# MegaFDC.net
KiCad netlist of a schematic drawn in EAGLE
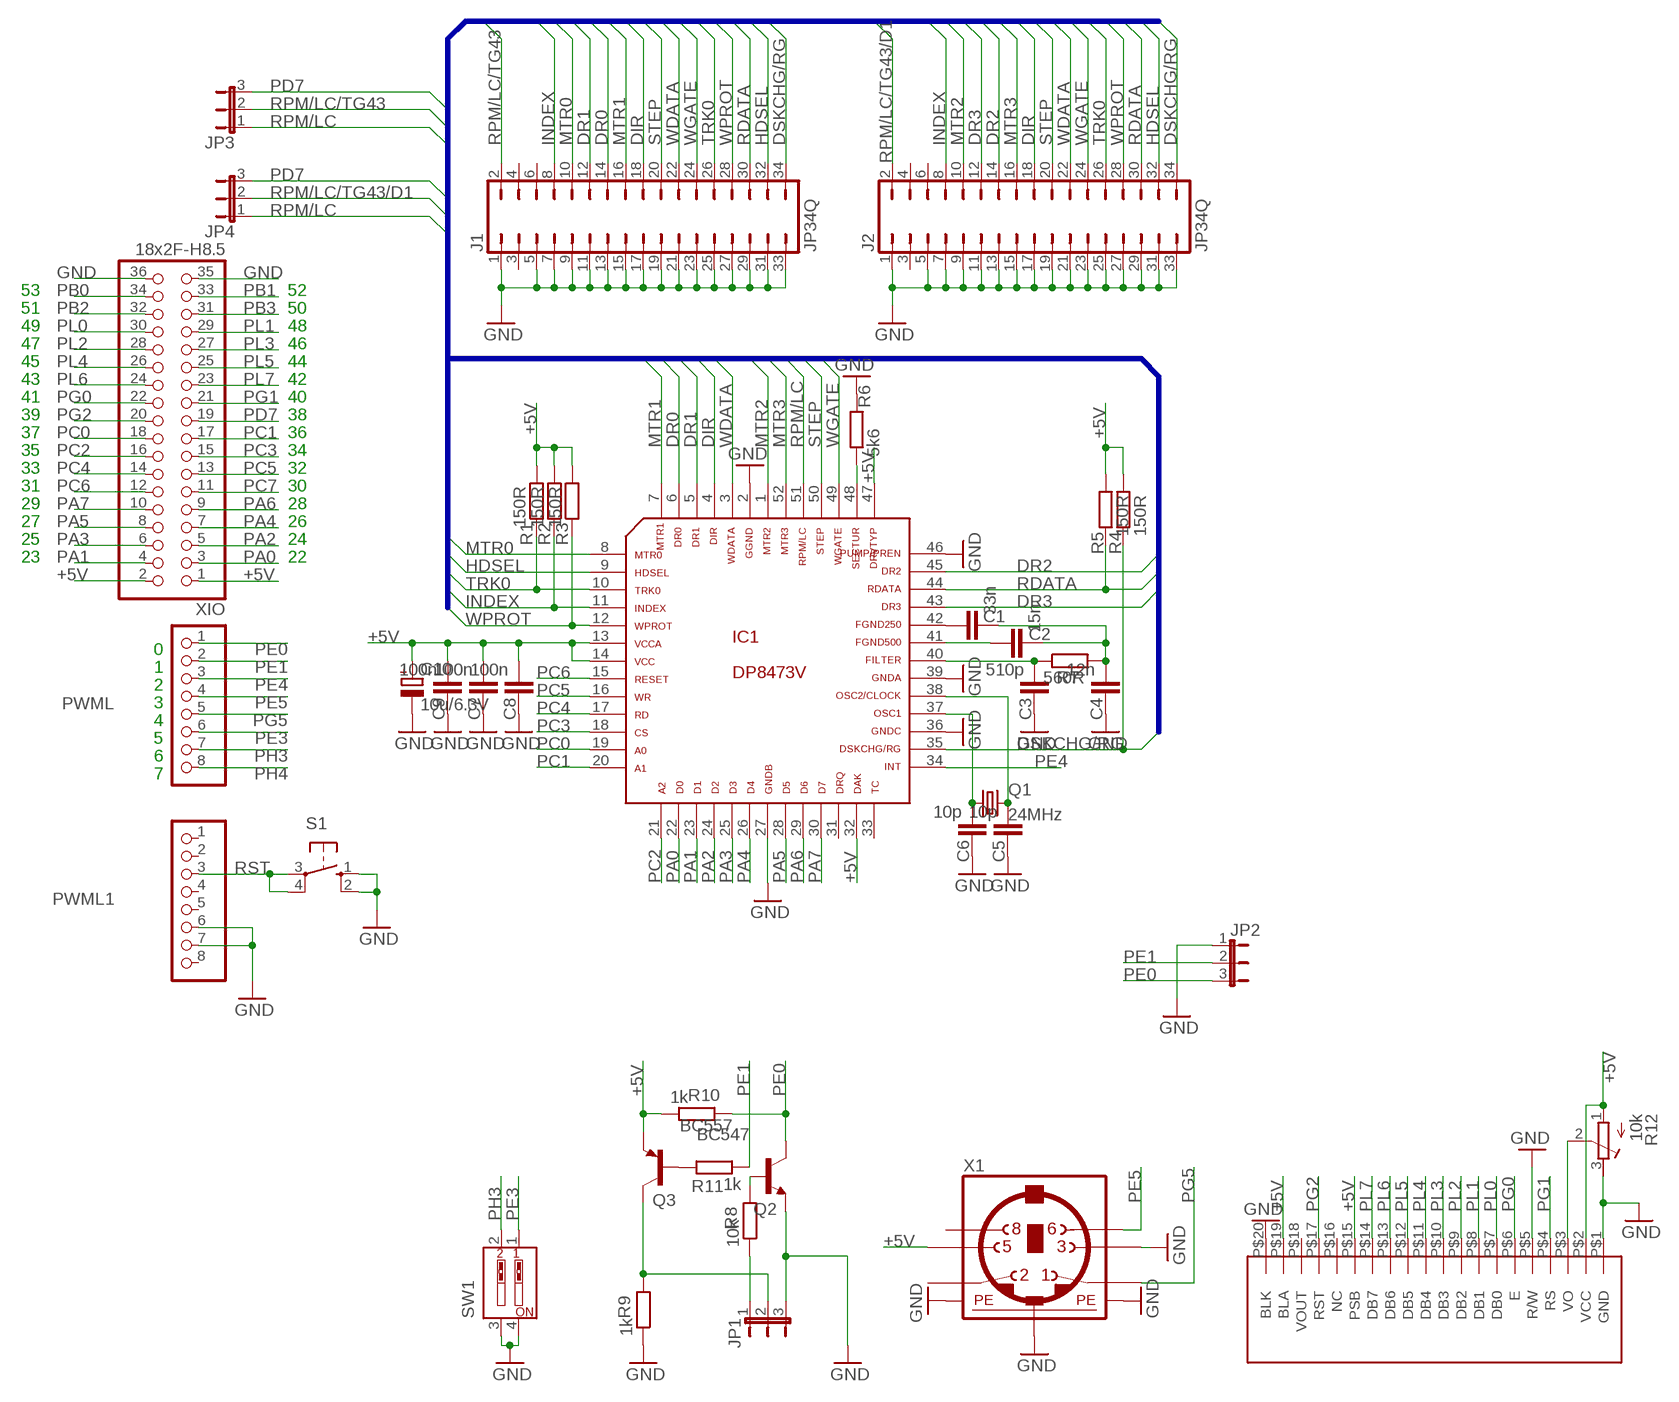
[diagram p0: schematic, sheet 1]

(export (version "E")
  (design (tool "Eeschema 10.0.6"))
  (components
    (comp (ref "C1")
      (value "33n")
      (footprint "eagle-import:C025-025X050")
      (libsource (lib "eagle-import") (part "C-EU025-025X050"))
    )
    (comp (ref "C2")
      (value "15n")
      (footprint "eagle-import:C025-025X050")
      (libsource (lib "eagle-import") (part "C-EU025-025X050"))
    )
    (comp (ref "C3")
      (value "510p")
      (footprint "eagle-import:C025-025X050")
      (libsource (lib "eagle-import") (part "C-EU025-025X050"))
    )
    (comp (ref "C4")
      (value "12n")
      (footprint "eagle-import:C025-025X050")
      (libsource (lib "eagle-import") (part "C-EU025-025X050"))
    )
    (comp (ref "C5")
      (value "10p")
      (footprint "eagle-import:C025-025X050")
      (libsource (lib "eagle-import") (part "C-EU025-025X050"))
    )
    (comp (ref "C6")
      (value "10p")
      (footprint "eagle-import:C025-025X050")
      (libsource (lib "eagle-import") (part "C-EU025-025X050"))
    )
    (comp (ref "C7")
      (value "100n")
      (footprint "eagle-import:C050-025X075")
      (libsource (lib "eagle-import") (part "C-EU050-025X075"))
    )
    (comp (ref "C8")
      (value "100n")
      (footprint "eagle-import:C050-025X075")
      (libsource (lib "eagle-import") (part "C-EU050-025X075"))
    )
    (comp (ref "C9")
      (value "100n")
      (footprint "eagle-import:C050-025X075")
      (libsource (lib "eagle-import") (part "C-EU050-025X075"))
    )
    (comp (ref "C10")
      (value "10u/6.3V")
      (footprint "eagle-import:B45181A")
      (libsource (lib "eagle-import") (part "CPOL-EUB45181A"))
    )
    (comp (ref "IC1")
      (value "DP8473V")
      (footprint "eagle-import:S52")
      (libsource (lib "eagle-import") (part "DP8473V{dblquote}"))
    )
    (comp (ref "J1")
      (value "JP34Q")
      (footprint "eagle-import:JP34Q")
      (libsource (lib "eagle-import") (part "JP34Q"))
    )
    (comp (ref "J2")
      (value "JP34Q")
      (footprint "eagle-import:JP34Q")
      (libsource (lib "eagle-import") (part "JP34Q"))
    )
    (comp (ref "JP1")
      (value "JP2E")
      (footprint "eagle-import:JP2")
      (libsource (lib "eagle-import") (part "JP2E"))
    )
    (comp (ref "JP2")
      (value "JP2E")
      (footprint "eagle-import:JP2")
      (libsource (lib "eagle-import") (part "JP2E"))
    )
    (comp (ref "JP3")
      (value "JP2E")
      (footprint "eagle-import:JP2")
      (libsource (lib "eagle-import") (part "JP2E"))
    )
    (comp (ref "JP4")
      (value "JP2E")
      (footprint "eagle-import:JP2")
      (libsource (lib "eagle-import") (part "JP2E"))
    )
    (comp (ref "PWML")
      (value "8x1F-H8.5")
      (footprint "eagle-import:1X08")
      (libsource (lib "eagle-import") (part "PINHD-1X8"))
    )
    (comp (ref "PWML1")
      (value "8x1F-H8.5")
      (footprint "eagle-import:1X08")
      (libsource (lib "eagle-import") (part "PINHD-1X8"))
    )
    (comp (ref "Q1")
      (value "24MHz")
      (footprint "eagle-import:HC49_S")
      (libsource (lib "eagle-import") (part "CRYSTALHC49S"))
    )
    (comp (ref "Q2")
      (value "BC547")
      (footprint "eagle-import:TO92S")
      (libsource (lib "eagle-import") (part "BC547S"))
    )
    (comp (ref "Q3")
      (value "BC557")
      (footprint "eagle-import:TO92-EBC")
      (libsource (lib "eagle-import") (part "BC557"))
    )
    (comp (ref "R1")
      (value "150R")
      (footprint "eagle-import:0207_7")
      (libsource (lib "eagle-import") (part "R-EU_0207/7"))
    )
    (comp (ref "R2")
      (value "150R")
      (footprint "eagle-import:0207_7")
      (libsource (lib "eagle-import") (part "R-EU_0207/7"))
    )
    (comp (ref "R3")
      (value "150R")
      (footprint "eagle-import:0207_7")
      (libsource (lib "eagle-import") (part "R-EU_0207/7"))
    )
    (comp (ref "R4")
      (value "150R")
      (footprint "eagle-import:0207_7")
      (libsource (lib "eagle-import") (part "R-EU_0207/7"))
    )
    (comp (ref "R5")
      (value "150R")
      (footprint "eagle-import:0207_7")
      (libsource (lib "eagle-import") (part "R-EU_0207/7"))
    )
    (comp (ref "R6")
      (value "5k6")
      (footprint "eagle-import:0207_7")
      (libsource (lib "eagle-import") (part "R-EU_0207/7"))
    )
    (comp (ref "R7")
      (value "560R")
      (footprint "eagle-import:0207_7")
      (libsource (lib "eagle-import") (part "R-EU_0207/7"))
    )
    (comp (ref "R8")
      (value "10k")
      (footprint "eagle-import:0207_7")
      (libsource (lib "eagle-import") (part "R-EU_0207/7"))
    )
    (comp (ref "R9")
      (value "1k")
      (footprint "eagle-import:0207_7")
      (libsource (lib "eagle-import") (part "R-EU_0207/7"))
    )
    (comp (ref "R10")
      (value "1k")
      (footprint "eagle-import:0207_7")
      (libsource (lib "eagle-import") (part "R-EU_0207/7"))
    )
    (comp (ref "R11")
      (value "1k")
      (footprint "eagle-import:0207_7")
      (libsource (lib "eagle-import") (part "R-EU_0207/7"))
    )
    (comp (ref "R12")
      (value "10k")
      (footprint "eagle-import:RTRIM3296Y")
      (libsource (lib "eagle-import") (part "R-TRIMM3296Y"))
    )
    (comp (ref "S1")
      (value "10-XX")
      (footprint "eagle-import:B3F-10XX")
      (fields (field (name "MPN") "B3F-1000"))
      (libsource (lib "eagle-import") (part "10-XX"))
    )
    (comp (ref "SW1")
      (value "DIP2X")
      (footprint "eagle-import:EDG-02")
      (libsource (lib "eagle-import") (part "DIP2X"))
    )
    (comp (ref "U$1")
      (value "W12864")
      (footprint "eagle-import:W12864")
      (libsource (lib "eagle-import") (part "W12864"))
    )
    (comp (ref "X1")
      (value "MINI_DIN_6")
      (footprint "eagle-import:M_DIN6")
      (libsource (lib "eagle-import") (part "MINI_DIN_6"))
    )
    (comp (ref "XIO")
      (value "18x2F-H8.5")
      (footprint "eagle-import:2X18")
      (libsource (lib "eagle-import") (part "PINHD-2X18"))
    )
  )
  (nets
    (net (code "1") (name "/+5V") (class "Default")
      (node (ref "C10") (pin "+") (pinfunction "+_+") (pintype "passive"))
      (node (ref "C7") (pin "2") (pinfunction "2_2") (pintype "passive"))
      (node (ref "C8") (pin "2") (pinfunction "2_2") (pintype "passive"))
      (node (ref "C9") (pin "2") (pinfunction "2_2") (pintype "passive"))
      (node (ref "IC1") (pin "13") (pinfunction "P$13_13") (pintype "bidirectional"))
      (node (ref "IC1") (pin "14") (pinfunction "P$14_14") (pintype "power_in"))
      (node (ref "IC1") (pin "32") (pinfunction "P$32_32") (pintype "bidirectional"))
      (node (ref "IC1") (pin "47") (pinfunction "P$47_47") (pintype "power_in"))
      (node (ref "Q3") (pin "E") (pinfunction "E_E") (pintype "passive"))
      (node (ref "R1") (pin "2") (pinfunction "2_2") (pintype "passive"))
      (node (ref "R10") (pin "1") (pinfunction "1_1") (pintype "passive"))
      (node (ref "R12") (pin "1") (pinfunction "A_1") (pintype "passive"))
      (node (ref "R2") (pin "2") (pinfunction "2_2") (pintype "passive"))
      (node (ref "R3") (pin "2") (pinfunction "2_2") (pintype "passive"))
      (node (ref "R4") (pin "2") (pinfunction "2_2") (pintype "passive"))
      (node (ref "R5") (pin "2") (pinfunction "2_2") (pintype "passive"))
      (node (ref "U$1") (pin "P$15") (pinfunction "PSB_P$15") (pintype "bidirectional"))
      (node (ref "U$1") (pin "P$19") (pinfunction "BLA_P$19") (pintype "bidirectional"))
      (node (ref "U$1") (pin "P$2") (pinfunction "VCC_P$2") (pintype "bidirectional"))
      (node (ref "X1") (pin "5") (pinfunction "5_5") (pintype "passive"))
      (node (ref "XIO") (pin "1") (pinfunction "1_1") (pintype "passive"))
      (node (ref "XIO") (pin "2") (pinfunction "2_2") (pintype "passive"))
    )
    (net (code "2") (name "/DIR") (class "Default")
      (node (ref "IC1") (pin "4") (pinfunction "P$4_4") (pintype "bidirectional"))
      (node (ref "J1") (pin "18") (pinfunction "18_18") (pintype "passive"))
      (node (ref "J2") (pin "18") (pinfunction "18_18") (pintype "passive"))
    )
    (net (code "3") (name "/DR0") (class "Default")
      (node (ref "IC1") (pin "6") (pinfunction "P$6_6") (pintype "bidirectional"))
      (node (ref "J1") (pin "14") (pinfunction "14_14") (pintype "passive"))
    )
    (net (code "4") (name "/DR1") (class "Default")
      (node (ref "IC1") (pin "5") (pinfunction "P$5_5") (pintype "bidirectional"))
      (node (ref "J1") (pin "12") (pinfunction "12_12") (pintype "passive"))
    )
    (net (code "5") (name "/DR2") (class "Default")
      (node (ref "IC1") (pin "45") (pinfunction "P$45_45") (pintype "bidirectional"))
      (node (ref "J2") (pin "14") (pinfunction "14_14") (pintype "passive"))
    )
    (net (code "6") (name "/DR3") (class "Default")
      (node (ref "IC1") (pin "43") (pinfunction "P$43_43") (pintype "bidirectional"))
      (node (ref "J2") (pin "12") (pinfunction "12_12") (pintype "passive"))
    )
    (net (code "7") (name "/DSKCHG{slash}RG") (class "Default")
      (node (ref "IC1") (pin "35") (pinfunction "P$35_35") (pintype "bidirectional"))
      (node (ref "J1") (pin "34") (pinfunction "34_34") (pintype "passive"))
      (node (ref "J2") (pin "34") (pinfunction "34_34") (pintype "passive"))
      (node (ref "R4") (pin "1") (pinfunction "1_1") (pintype "passive"))
    )
    (net (code "8") (name "/HDSEL") (class "Default")
      (node (ref "IC1") (pin "9") (pinfunction "P$9_9") (pintype "bidirectional"))
      (node (ref "J1") (pin "32") (pinfunction "32_32") (pintype "passive"))
      (node (ref "J2") (pin "32") (pinfunction "32_32") (pintype "passive"))
    )
    (net (code "9") (name "/INDEX") (class "Default")
      (node (ref "IC1") (pin "11") (pinfunction "P$11_11") (pintype "bidirectional"))
      (node (ref "J1") (pin "8") (pinfunction "8_8") (pintype "passive"))
      (node (ref "J2") (pin "8") (pinfunction "8_8") (pintype "passive"))
      (node (ref "R2") (pin "1") (pinfunction "1_1") (pintype "passive"))
    )
    (net (code "10") (name "/MTR0") (class "Default")
      (node (ref "IC1") (pin "8") (pinfunction "P$8_8") (pintype "bidirectional"))
      (node (ref "J1") (pin "10") (pinfunction "10_10") (pintype "passive"))
    )
    (net (code "11") (name "/MTR1") (class "Default")
      (node (ref "IC1") (pin "7") (pinfunction "P$7_7") (pintype "bidirectional"))
      (node (ref "J1") (pin "16") (pinfunction "16_16") (pintype "passive"))
    )
    (net (code "12") (name "/MTR2") (class "Default")
      (node (ref "IC1") (pin "1") (pinfunction "P$1_1") (pintype "bidirectional"))
      (node (ref "J2") (pin "10") (pinfunction "10_10") (pintype "passive"))
    )
    (net (code "13") (name "/MTR3") (class "Default")
      (node (ref "IC1") (pin "52") (pinfunction "P$52_52") (pintype "bidirectional"))
      (node (ref "J2") (pin "16") (pinfunction "16_16") (pintype "passive"))
    )
    (net (code "14") (name "/PA0") (class "Default")
      (node (ref "IC1") (pin "22") (pinfunction "P$22_22") (pintype "bidirectional"))
      (node (ref "XIO") (pin "3") (pinfunction "3_3") (pintype "passive"))
    )
    (net (code "15") (name "/PA1") (class "Default")
      (node (ref "IC1") (pin "23") (pinfunction "P$23_23") (pintype "bidirectional"))
      (node (ref "XIO") (pin "4") (pinfunction "4_4") (pintype "passive"))
    )
    (net (code "16") (name "/PA2") (class "Default")
      (node (ref "IC1") (pin "24") (pinfunction "P$24_24") (pintype "bidirectional"))
      (node (ref "XIO") (pin "5") (pinfunction "5_5") (pintype "passive"))
    )
    (net (code "17") (name "/PA3") (class "Default")
      (node (ref "IC1") (pin "25") (pinfunction "P$25_25") (pintype "bidirectional"))
      (node (ref "XIO") (pin "6") (pinfunction "6_6") (pintype "passive"))
    )
    (net (code "18") (name "/PA4") (class "Default")
      (node (ref "IC1") (pin "26") (pinfunction "P$26_26") (pintype "bidirectional"))
      (node (ref "XIO") (pin "7") (pinfunction "7_7") (pintype "passive"))
    )
    (net (code "19") (name "/PA5") (class "Default")
      (node (ref "IC1") (pin "28") (pinfunction "P$28_28") (pintype "bidirectional"))
      (node (ref "XIO") (pin "8") (pinfunction "8_8") (pintype "passive"))
    )
    (net (code "20") (name "/PA6") (class "Default")
      (node (ref "IC1") (pin "29") (pinfunction "P$29_29") (pintype "bidirectional"))
      (node (ref "XIO") (pin "9") (pinfunction "9_9") (pintype "passive"))
    )
    (net (code "21") (name "/PA7") (class "Default")
      (node (ref "IC1") (pin "30") (pinfunction "P$30_30") (pintype "bidirectional"))
      (node (ref "XIO") (pin "10") (pinfunction "10_10") (pintype "passive"))
    )
    (net (code "22") (name "/PB0") (class "Default")
      (node (ref "XIO") (pin "34") (pinfunction "34_34") (pintype "passive"))
    )
    (net (code "23") (name "/PB1") (class "Default")
      (node (ref "XIO") (pin "33") (pinfunction "33_33") (pintype "passive"))
    )
    (net (code "24") (name "/PB2") (class "Default")
      (node (ref "XIO") (pin "32") (pinfunction "32_32") (pintype "passive"))
    )
    (net (code "25") (name "/PB3") (class "Default")
      (node (ref "XIO") (pin "31") (pinfunction "31_31") (pintype "passive"))
    )
    (net (code "26") (name "/PC0") (class "Default")
      (node (ref "IC1") (pin "19") (pinfunction "P$19_19") (pintype "bidirectional"))
      (node (ref "XIO") (pin "18") (pinfunction "18_18") (pintype "passive"))
    )
    (net (code "27") (name "/PC1") (class "Default")
      (node (ref "IC1") (pin "20") (pinfunction "P$20_20") (pintype "bidirectional"))
      (node (ref "XIO") (pin "17") (pinfunction "17_17") (pintype "passive"))
    )
    (net (code "28") (name "/PC2") (class "Default")
      (node (ref "IC1") (pin "21") (pinfunction "P$21_21") (pintype "bidirectional"))
      (node (ref "XIO") (pin "16") (pinfunction "16_16") (pintype "passive"))
    )
    (net (code "29") (name "/PC3") (class "Default")
      (node (ref "IC1") (pin "18") (pinfunction "P$18_18") (pintype "bidirectional"))
      (node (ref "XIO") (pin "15") (pinfunction "15_15") (pintype "passive"))
    )
    (net (code "30") (name "/PC4") (class "Default")
      (node (ref "IC1") (pin "17") (pinfunction "P$17_17") (pintype "bidirectional"))
      (node (ref "XIO") (pin "14") (pinfunction "14_14") (pintype "passive"))
    )
    (net (code "31") (name "/PC5") (class "Default")
      (node (ref "IC1") (pin "16") (pinfunction "P$16_16") (pintype "bidirectional"))
      (node (ref "XIO") (pin "13") (pinfunction "13_13") (pintype "passive"))
    )
    (net (code "32") (name "/PC6") (class "Default")
      (node (ref "IC1") (pin "15") (pinfunction "P$15_15") (pintype "power_in"))
      (node (ref "XIO") (pin "12") (pinfunction "12_12") (pintype "passive"))
    )
    (net (code "33") (name "/PC7") (class "Default")
      (node (ref "XIO") (pin "11") (pinfunction "11_11") (pintype "passive"))
    )
    (net (code "34") (name "/PD7") (class "Default")
      (node (ref "JP3") (pin "3") (pinfunction "3_3") (pintype "passive"))
      (node (ref "JP4") (pin "3") (pinfunction "3_3") (pintype "passive"))
      (node (ref "XIO") (pin "19") (pinfunction "19_19") (pintype "passive"))
    )
    (net (code "35") (name "/PE0") (class "Default")
      (node (ref "JP2") (pin "3") (pinfunction "3_3") (pintype "passive"))
      (node (ref "PWML") (pin "1") (pinfunction "1_1") (pintype "passive"))
      (node (ref "Q2") (pin "3") (pinfunction "C_3") (pintype "passive"))
      (node (ref "R10") (pin "2") (pinfunction "2_2") (pintype "passive"))
    )
    (net (code "36") (name "/PE1") (class "Default")
      (node (ref "JP2") (pin "2") (pinfunction "2_2") (pintype "passive"))
      (node (ref "PWML") (pin "2") (pinfunction "2_2") (pintype "passive"))
      (node (ref "R11") (pin "1") (pinfunction "1_1") (pintype "passive"))
    )
    (net (code "37") (name "/PE3") (class "Default")
      (node (ref "PWML") (pin "6") (pinfunction "6_6") (pintype "passive"))
      (node (ref "SW1") (pin "1") (pinfunction "1_1") (pintype "passive"))
    )
    (net (code "38") (name "/PE4") (class "Default")
      (node (ref "IC1") (pin "34") (pinfunction "P$34_34") (pintype "bidirectional"))
      (node (ref "PWML") (pin "3") (pinfunction "3_3") (pintype "passive"))
    )
    (net (code "39") (name "/PE5") (class "Default")
      (node (ref "PWML") (pin "4") (pinfunction "4_4") (pintype "passive"))
      (node (ref "X1") (pin "6") (pinfunction "6_6") (pintype "passive"))
    )
    (net (code "40") (name "/PG0") (class "Default")
      (node (ref "U$1") (pin "P$6") (pinfunction "E_P$6") (pintype "bidirectional"))
      (node (ref "XIO") (pin "22") (pinfunction "22_22") (pintype "passive"))
    )
    (net (code "41") (name "/PG1") (class "Default")
      (node (ref "U$1") (pin "P$4") (pinfunction "RS_P$4") (pintype "bidirectional"))
      (node (ref "XIO") (pin "21") (pinfunction "21_21") (pintype "passive"))
    )
    (net (code "42") (name "/PG2") (class "Default")
      (node (ref "U$1") (pin "P$17") (pinfunction "RST_P$17") (pintype "bidirectional"))
      (node (ref "XIO") (pin "20") (pinfunction "20_20") (pintype "passive"))
    )
    (net (code "43") (name "/PG5") (class "Default")
      (node (ref "PWML") (pin "5") (pinfunction "5_5") (pintype "passive"))
      (node (ref "X1") (pin "1") (pinfunction "1_1") (pintype "passive"))
    )
    (net (code "44") (name "/PH3") (class "Default")
      (node (ref "PWML") (pin "7") (pinfunction "7_7") (pintype "passive"))
      (node (ref "SW1") (pin "2") (pinfunction "2_2") (pintype "passive"))
    )
    (net (code "45") (name "/PH4") (class "Default")
      (node (ref "PWML") (pin "8") (pinfunction "8_8") (pintype "passive"))
    )
    (net (code "46") (name "/PL0") (class "Default")
      (node (ref "U$1") (pin "P$7") (pinfunction "DB0_P$7") (pintype "bidirectional"))
      (node (ref "XIO") (pin "30") (pinfunction "30_30") (pintype "passive"))
    )
    (net (code "47") (name "/PL1") (class "Default")
      (node (ref "U$1") (pin "P$8") (pinfunction "DB1_P$8") (pintype "bidirectional"))
      (node (ref "XIO") (pin "29") (pinfunction "29_29") (pintype "passive"))
    )
    (net (code "48") (name "/PL2") (class "Default")
      (node (ref "U$1") (pin "P$9") (pinfunction "DB2_P$9") (pintype "bidirectional"))
      (node (ref "XIO") (pin "28") (pinfunction "28_28") (pintype "passive"))
    )
    (net (code "49") (name "/PL3") (class "Default")
      (node (ref "U$1") (pin "P$10") (pinfunction "DB3_P$10") (pintype "bidirectional"))
      (node (ref "XIO") (pin "27") (pinfunction "27_27") (pintype "passive"))
    )
    (net (code "50") (name "/PL4") (class "Default")
      (node (ref "U$1") (pin "P$11") (pinfunction "DB4_P$11") (pintype "bidirectional"))
      (node (ref "XIO") (pin "26") (pinfunction "26_26") (pintype "passive"))
    )
    (net (code "51") (name "/PL5") (class "Default")
      (node (ref "U$1") (pin "P$12") (pinfunction "DB5_P$12") (pintype "bidirectional"))
      (node (ref "XIO") (pin "25") (pinfunction "25_25") (pintype "passive"))
    )
    (net (code "52") (name "/PL6") (class "Default")
      (node (ref "U$1") (pin "P$13") (pinfunction "DB6_P$13") (pintype "bidirectional"))
      (node (ref "XIO") (pin "24") (pinfunction "24_24") (pintype "passive"))
    )
    (net (code "53") (name "/PL7") (class "Default")
      (node (ref "U$1") (pin "P$14") (pinfunction "DB7_P$14") (pintype "bidirectional"))
      (node (ref "XIO") (pin "23") (pinfunction "23_23") (pintype "passive"))
    )
    (net (code "54") (name "/RDATA") (class "Default")
      (node (ref "IC1") (pin "44") (pinfunction "P$44_44") (pintype "bidirectional"))
      (node (ref "J1") (pin "30") (pinfunction "30_30") (pintype "passive"))
      (node (ref "J2") (pin "30") (pinfunction "30_30") (pintype "passive"))
      (node (ref "R5") (pin "1") (pinfunction "1_1") (pintype "passive"))
    )
    (net (code "55") (name "/RPM{slash}LC") (class "Default")
      (node (ref "IC1") (pin "51") (pinfunction "P$51_51") (pintype "bidirectional"))
      (node (ref "JP3") (pin "1") (pinfunction "1_1") (pintype "passive"))
      (node (ref "JP4") (pin "1") (pinfunction "1_1") (pintype "passive"))
    )
    (net (code "56") (name "/RPM{slash}LC{slash}TG43") (class "Default")
      (node (ref "J1") (pin "2") (pinfunction "2_2") (pintype "passive"))
      (node (ref "JP3") (pin "2") (pinfunction "2_2") (pintype "passive"))
    )
    (net (code "57") (name "/RPM{slash}LC{slash}TG43{slash}D1") (class "Default")
      (node (ref "J2") (pin "2") (pinfunction "2_2") (pintype "passive"))
      (node (ref "JP4") (pin "2") (pinfunction "2_2") (pintype "passive"))
    )
    (net (code "58") (name "/RST") (class "Default")
      (node (ref "PWML1") (pin "3") (pinfunction "3_3") (pintype "passive"))
      (node (ref "S1") (pin "3") (pinfunction "P_3") (pintype "passive"))
      (node (ref "S1") (pin "4") (pinfunction "P1_4") (pintype "passive"))
    )
    (net (code "59") (name "/STEP") (class "Default")
      (node (ref "IC1") (pin "50") (pinfunction "P$50_50") (pintype "bidirectional"))
      (node (ref "J1") (pin "20") (pinfunction "20_20") (pintype "passive"))
      (node (ref "J2") (pin "20") (pinfunction "20_20") (pintype "passive"))
    )
    (net (code "60") (name "/TRK0") (class "Default")
      (node (ref "IC1") (pin "10") (pinfunction "P$10_10") (pintype "bidirectional"))
      (node (ref "J1") (pin "26") (pinfunction "26_26") (pintype "passive"))
      (node (ref "J2") (pin "26") (pinfunction "26_26") (pintype "passive"))
      (node (ref "R1") (pin "1") (pinfunction "1_1") (pintype "passive"))
    )
    (net (code "61") (name "/WDATA") (class "Default")
      (node (ref "IC1") (pin "3") (pinfunction "P$3_3") (pintype "bidirectional"))
      (node (ref "J1") (pin "22") (pinfunction "22_22") (pintype "passive"))
      (node (ref "J2") (pin "22") (pinfunction "22_22") (pintype "passive"))
    )
    (net (code "62") (name "/WGATE") (class "Default")
      (node (ref "IC1") (pin "49") (pinfunction "P$49_49") (pintype "bidirectional"))
      (node (ref "J1") (pin "24") (pinfunction "24_24") (pintype "passive"))
      (node (ref "J2") (pin "24") (pinfunction "24_24") (pintype "passive"))
    )
    (net (code "63") (name "/WPROT") (class "Default")
      (node (ref "IC1") (pin "12") (pinfunction "P$12_12") (pintype "bidirectional"))
      (node (ref "J1") (pin "28") (pinfunction "28_28") (pintype "passive"))
      (node (ref "J2") (pin "28") (pinfunction "28_28") (pintype "passive"))
      (node (ref "R3") (pin "1") (pinfunction "1_1") (pintype "passive"))
    )
    (net (code "64") (name "GND") (class "Default")
      (node (ref "C10") (pin "-") (pinfunction "-_-") (pintype "passive"))
      (node (ref "C3") (pin "1") (pinfunction "1_1") (pintype "passive"))
      (node (ref "C4") (pin "1") (pinfunction "1_1") (pintype "passive"))
      (node (ref "C5") (pin "1") (pinfunction "1_1") (pintype "passive"))
      (node (ref "C6") (pin "1") (pinfunction "1_1") (pintype "passive"))
      (node (ref "C7") (pin "1") (pinfunction "1_1") (pintype "passive"))
      (node (ref "C8") (pin "1") (pinfunction "1_1") (pintype "passive"))
      (node (ref "C9") (pin "1") (pinfunction "1_1") (pintype "passive"))
      (node (ref "IC1") (pin "2") (pinfunction "P$2_2") (pintype "power_in"))
      (node (ref "IC1") (pin "27") (pinfunction "P$27_27") (pintype "bidirectional"))
      (node (ref "IC1") (pin "36") (pinfunction "P$36_36") (pintype "power_in"))
      (node (ref "IC1") (pin "39") (pinfunction "P$39_39") (pintype "power_in"))
      (node (ref "IC1") (pin "46") (pinfunction "P$46_46") (pintype "power_in"))
      (node (ref "J1") (pin "1") (pinfunction "1_1") (pintype "passive"))
      (node (ref "J1") (pin "11") (pinfunction "11_11") (pintype "passive"))
      (node (ref "J1") (pin "13") (pinfunction "13_13") (pintype "passive"))
      (node (ref "J1") (pin "15") (pinfunction "15_15") (pintype "passive"))
      (node (ref "J1") (pin "17") (pinfunction "17_17") (pintype "passive"))
      (node (ref "J1") (pin "19") (pinfunction "19_19") (pintype "passive"))
      (node (ref "J1") (pin "21") (pinfunction "21_21") (pintype "passive"))
      (node (ref "J1") (pin "23") (pinfunction "23_23") (pintype "passive"))
      (node (ref "J1") (pin "25") (pinfunction "25_25") (pintype "passive"))
      (node (ref "J1") (pin "27") (pinfunction "27_27") (pintype "passive"))
      (node (ref "J1") (pin "29") (pinfunction "29_29") (pintype "passive"))
      (node (ref "J1") (pin "31") (pinfunction "31_31") (pintype "passive"))
      (node (ref "J1") (pin "33") (pinfunction "33_33") (pintype "passive"))
      (node (ref "J1") (pin "5") (pinfunction "5_5") (pintype "passive"))
      (node (ref "J1") (pin "7") (pinfunction "7_7") (pintype "passive"))
      (node (ref "J1") (pin "9") (pinfunction "9_9") (pintype "passive"))
      (node (ref "J2") (pin "1") (pinfunction "1_1") (pintype "passive"))
      (node (ref "J2") (pin "11") (pinfunction "11_11") (pintype "passive"))
      (node (ref "J2") (pin "13") (pinfunction "13_13") (pintype "passive"))
      (node (ref "J2") (pin "15") (pinfunction "15_15") (pintype "passive"))
      (node (ref "J2") (pin "17") (pinfunction "17_17") (pintype "passive"))
      (node (ref "J2") (pin "19") (pinfunction "19_19") (pintype "passive"))
      (node (ref "J2") (pin "21") (pinfunction "21_21") (pintype "passive"))
      (node (ref "J2") (pin "23") (pinfunction "23_23") (pintype "passive"))
      (node (ref "J2") (pin "25") (pinfunction "25_25") (pintype "passive"))
      (node (ref "J2") (pin "27") (pinfunction "27_27") (pintype "passive"))
      (node (ref "J2") (pin "29") (pinfunction "29_29") (pintype "passive"))
      (node (ref "J2") (pin "31") (pinfunction "31_31") (pintype "passive"))
      (node (ref "J2") (pin "33") (pinfunction "33_33") (pintype "passive"))
      (node (ref "J2") (pin "5") (pinfunction "5_5") (pintype "passive"))
      (node (ref "J2") (pin "7") (pinfunction "7_7") (pintype "passive"))
      (node (ref "J2") (pin "9") (pinfunction "9_9") (pintype "passive"))
      (node (ref "JP1") (pin "3") (pinfunction "3_3") (pintype "passive"))
      (node (ref "JP2") (pin "1") (pinfunction "1_1") (pintype "passive"))
      (node (ref "PWML1") (pin "6") (pinfunction "6_6") (pintype "passive"))
      (node (ref "PWML1") (pin "7") (pinfunction "7_7") (pintype "passive"))
      (node (ref "Q2") (pin "1") (pinfunction "E_1") (pintype "passive"))
      (node (ref "R12") (pin "3") (pinfunction "E_3") (pintype "passive"))
      (node (ref "R6") (pin "2") (pinfunction "2_2") (pintype "passive"))
      (node (ref "R9") (pin "1") (pinfunction "1_1") (pintype "passive"))
      (node (ref "S1") (pin "1") (pinfunction "S_1") (pintype "passive"))
      (node (ref "S1") (pin "2") (pinfunction "S1_2") (pintype "passive"))
      (node (ref "SW1") (pin "3") (pinfunction "3_3") (pintype "passive"))
      (node (ref "SW1") (pin "4") (pinfunction "4_4") (pintype "passive"))
      (node (ref "U$1") (pin "P$1") (pinfunction "GND_P$1") (pintype "bidirectional"))
      (node (ref "U$1") (pin "P$20") (pinfunction "BLK_P$20") (pintype "bidirectional"))
      (node (ref "U$1") (pin "P$5") (pinfunction "R/W_P$5") (pintype "bidirectional"))
      (node (ref "X1") (pin "3") (pinfunction "3_3") (pintype "passive"))
      (node (ref "X1") (pin "SH1") (pinfunction "PE1_SH1") (pintype "power_in"))
      (node (ref "X1") (pin "SH2") (pinfunction "PE2_SH2") (pintype "power_in"))
      (node (ref "X1") (pin "SH3") (pinfunction "PE3_SH3") (pintype "power_in"))
      (node (ref "XIO") (pin "35") (pinfunction "35_35") (pintype "passive"))
      (node (ref "XIO") (pin "36") (pinfunction "36_36") (pintype "passive"))
    )
    (net (code "65") (name "Net-(C1-Pad2)") (class "Default")
      (node (ref "C1") (pin "2") (pinfunction "2_2") (pintype "passive"))
      (node (ref "C2") (pin "2") (pinfunction "2_2") (pintype "passive"))
      (node (ref "C4") (pin "2") (pinfunction "2_2") (pintype "passive"))
      (node (ref "R7") (pin "2") (pinfunction "2_2") (pintype "passive"))
    )
    (net (code "66") (name "Net-(IC1-P$37)") (class "Default")
      (node (ref "C6") (pin "2") (pinfunction "2_2") (pintype "passive"))
      (node (ref "IC1") (pin "37") (pinfunction "P$37_37") (pintype "bidirectional"))
      (node (ref "Q1") (pin "1") (pinfunction "1_1") (pintype "passive"))
    )
    (net (code "67") (name "Net-(IC1-P$38)") (class "Default")
      (node (ref "C5") (pin "2") (pinfunction "2_2") (pintype "passive"))
      (node (ref "IC1") (pin "38") (pinfunction "P$38_38") (pintype "bidirectional"))
      (node (ref "Q1") (pin "2") (pinfunction "2_2") (pintype "passive"))
    )
    (net (code "68") (name "Net-(IC1-P$40)") (class "Default")
      (node (ref "C3") (pin "2") (pinfunction "2_2") (pintype "passive"))
      (node (ref "IC1") (pin "40") (pinfunction "P$40_40") (pintype "bidirectional"))
      (node (ref "R7") (pin "1") (pinfunction "1_1") (pintype "passive"))
    )
    (net (code "69") (name "Net-(IC1-P$41)") (class "Default")
      (node (ref "C2") (pin "1") (pinfunction "1_1") (pintype "passive"))
      (node (ref "IC1") (pin "41") (pinfunction "P$41_41") (pintype "bidirectional"))
    )
    (net (code "70") (name "Net-(IC1-P$42)") (class "Default")
      (node (ref "C1") (pin "1") (pinfunction "1_1") (pintype "passive"))
      (node (ref "IC1") (pin "42") (pinfunction "P$42_42") (pintype "bidirectional"))
    )
    (net (code "71") (name "Net-(IC1-P$48)") (class "Default")
      (node (ref "IC1") (pin "48") (pinfunction "P$48_48") (pintype "bidirectional"))
      (node (ref "R6") (pin "1") (pinfunction "1_1") (pintype "passive"))
    )
    (net (code "72") (name "Net-(JP1-Pad1)") (class "Default")
      (node (ref "JP1") (pin "1") (pinfunction "1_1") (pintype "passive"))
      (node (ref "R8") (pin "1") (pinfunction "1_1") (pintype "passive"))
    )
    (net (code "73") (name "Net-(JP1-Pad2)") (class "Default")
      (node (ref "JP1") (pin "2") (pinfunction "2_2") (pintype "passive"))
      (node (ref "Q3") (pin "C") (pinfunction "C_C") (pintype "passive"))
      (node (ref "R9") (pin "2") (pinfunction "2_2") (pintype "passive"))
    )
    (net (code "74") (name "Net-(Q2-B)") (class "Default")
      (node (ref "Q2") (pin "2") (pinfunction "B_2") (pintype "passive"))
      (node (ref "R8") (pin "2") (pinfunction "2_2") (pintype "passive"))
    )
    (net (code "75") (name "Net-(Q3-PadB)") (class "Default")
      (node (ref "Q3") (pin "B") (pinfunction "B_B") (pintype "passive"))
      (node (ref "R11") (pin "2") (pinfunction "2_2") (pintype "passive"))
    )
    (net (code "76") (name "Net-(R12-S)") (class "Default")
      (node (ref "R12") (pin "2") (pinfunction "S_2") (pintype "passive"))
      (node (ref "U$1") (pin "P$3") (pinfunction "VO_P$3") (pintype "bidirectional"))
    )
    (net (code "77") (name "unconnected-(IC1-P$31-Pad31)") (class "Default")
      (node (ref "IC1") (pin "31") (pinfunction "P$31_31") (pintype "bidirectional"))
    )
    (net (code "78") (name "unconnected-(IC1-P$33-Pad33)") (class "Default")
      (node (ref "IC1") (pin "33") (pinfunction "P$33_33") (pintype "bidirectional"))
    )
    (net (code "79") (name "unconnected-(J1-Pad3)") (class "Default")
      (node (ref "J1") (pin "3") (pinfunction "3_3") (pintype "passive"))
    )
    (net (code "80") (name "unconnected-(J1-Pad4)") (class "Default")
      (node (ref "J1") (pin "4") (pinfunction "4_4") (pintype "passive"))
    )
    (net (code "81") (name "unconnected-(J1-Pad6)") (class "Default")
      (node (ref "J1") (pin "6") (pinfunction "6_6") (pintype "passive"))
    )
    (net (code "82") (name "unconnected-(J2-Pad3)") (class "Default")
      (node (ref "J2") (pin "3") (pinfunction "3_3") (pintype "passive"))
    )
    (net (code "83") (name "unconnected-(J2-Pad4)") (class "Default")
      (node (ref "J2") (pin "4") (pinfunction "4_4") (pintype "passive"))
    )
    (net (code "84") (name "unconnected-(J2-Pad6)") (class "Default")
      (node (ref "J2") (pin "6") (pinfunction "6_6") (pintype "passive"))
    )
    (net (code "85") (name "unconnected-(PWML1-Pad1)") (class "Default")
      (node (ref "PWML1") (pin "1") (pinfunction "1_1") (pintype "passive"))
    )
    (net (code "86") (name "unconnected-(PWML1-Pad2)") (class "Default")
      (node (ref "PWML1") (pin "2") (pinfunction "2_2") (pintype "passive"))
    )
    (net (code "87") (name "unconnected-(PWML1-Pad4)") (class "Default")
      (node (ref "PWML1") (pin "4") (pinfunction "4_4") (pintype "passive"))
    )
    (net (code "88") (name "unconnected-(PWML1-Pad5)") (class "Default")
      (node (ref "PWML1") (pin "5") (pinfunction "5_5") (pintype "passive"))
    )
    (net (code "89") (name "unconnected-(PWML1-Pad8)") (class "Default")
      (node (ref "PWML1") (pin "8") (pinfunction "8_8") (pintype "passive"))
    )
    (net (code "90") (name "unconnected-(U$1-NC-PadP$16)") (class "Default")
      (node (ref "U$1") (pin "P$16") (pinfunction "NC_P$16") (pintype "bidirectional"))
    )
    (net (code "91") (name "unconnected-(U$1-VOUT-PadP$18)") (class "Default")
      (node (ref "U$1") (pin "P$18") (pinfunction "VOUT_P$18") (pintype "bidirectional"))
    )
    (net (code "92") (name "unconnected-(X1-Pad2)") (class "Default")
      (node (ref "X1") (pin "2") (pinfunction "2_2") (pintype "passive"))
    )
    (net (code "93") (name "unconnected-(X1-Pad8)") (class "Default")
      (node (ref "X1") (pin "8") (pinfunction "8_8") (pintype "passive"))
    )
  )
)
